# DS18B20_breakout.net
KiCad netlist of a schematic drawn in EAGLE
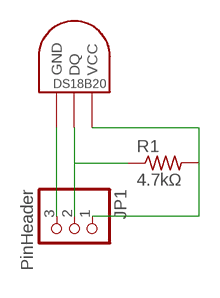
[diagram p0: schematic, sheet 1]

(export (version "E")
  (design (tool "Eeschema 10.0.6"))
  (components
    (comp (ref "JP1")
      (value "PinHeader")
      (footprint "eagle-import:1X03")
      (libsource (lib "eagle-import") (part "PINHD-1X3"))
    )
    (comp (ref "R1")
      (value "4.7kΩ")
      (footprint "eagle-import:0207_7")
      (libsource (lib "eagle-import") (part "R-US_0207/7"))
    )
    (comp (ref "U$1")
      (value "DS1820TO92")
      (footprint "eagle-import:DS1820")
      (libsource (lib "eagle-import") (part "DS1820TO92"))
    )
  )
  (nets
    (net (code "1") (name "Net-(JP1-Pad2)") (class "Default")
      (node (ref "JP1") (pin "2") (pinfunction "2_2") (pintype "passive"))
      (node (ref "R1") (pin "1") (pinfunction "1_1") (pintype "passive"))
      (node (ref "U$1") (pin "DQ") (pinfunction "DQ_DQ") (pintype "bidirectional"))
    )
    (net (code "2") (name "Net-(JP1-Pad3)") (class "Default")
      (node (ref "JP1") (pin "3") (pinfunction "3_3") (pintype "passive"))
      (node (ref "U$1") (pin "GND") (pinfunction "GND_GND") (pintype "power_in"))
    )
    (net (code "3") (name "Net-(U$1-VCC)") (class "Default")
      (node (ref "JP1") (pin "1") (pinfunction "1_1") (pintype "passive"))
      (node (ref "R1") (pin "2") (pinfunction "2_2") (pintype "passive"))
      (node (ref "U$1") (pin "VDD") (pinfunction "VCC_VDD") (pintype "power_in"))
    )
  )
)
